# Camera_Board.net
KiCad netlist of a schematic drawn in EAGLE
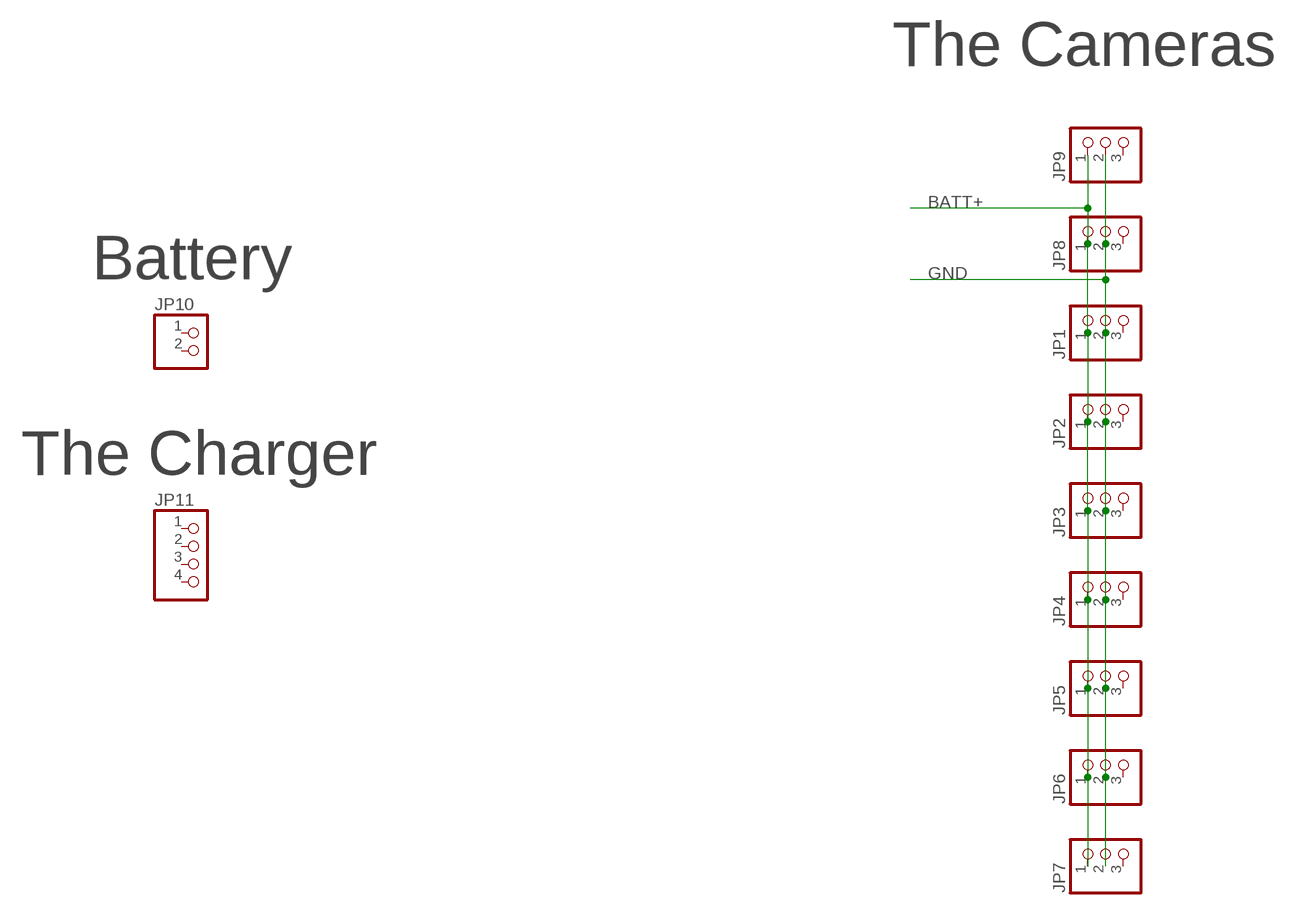
[diagram p0: schematic, sheet 1]

(export (version "E")
  (design (tool "Eeschema 10.0.6"))
  (components
    (comp (ref "JP1")
      (value "PINHD-1X3")
      (footprint "eagle-import:1X03")
      (libsource (lib "eagle-import") (part "PINHD-1X3"))
    )
    (comp (ref "JP2")
      (value "PINHD-1X3")
      (footprint "eagle-import:1X03")
      (libsource (lib "eagle-import") (part "PINHD-1X3"))
    )
    (comp (ref "JP3")
      (value "PINHD-1X3")
      (footprint "eagle-import:1X03")
      (libsource (lib "eagle-import") (part "PINHD-1X3"))
    )
    (comp (ref "JP4")
      (value "PINHD-1X3")
      (footprint "eagle-import:1X03")
      (libsource (lib "eagle-import") (part "PINHD-1X3"))
    )
    (comp (ref "JP5")
      (value "PINHD-1X3")
      (footprint "eagle-import:1X03")
      (libsource (lib "eagle-import") (part "PINHD-1X3"))
    )
    (comp (ref "JP6")
      (value "PINHD-1X3")
      (footprint "eagle-import:1X03")
      (libsource (lib "eagle-import") (part "PINHD-1X3"))
    )
    (comp (ref "JP7")
      (value "PINHD-1X3")
      (footprint "eagle-import:1X03")
      (libsource (lib "eagle-import") (part "PINHD-1X3"))
    )
    (comp (ref "JP8")
      (value "PINHD-1X3")
      (footprint "eagle-import:1X03")
      (libsource (lib "eagle-import") (part "PINHD-1X3"))
    )
    (comp (ref "JP9")
      (value "PINHD-1X3")
      (footprint "eagle-import:1X03")
      (libsource (lib "eagle-import") (part "PINHD-1X3"))
    )
    (comp (ref "JP10")
      (value "PINHD-1X2")
      (footprint "eagle-import:1X02")
      (libsource (lib "eagle-import") (part "PINHD-1X2"))
    )
    (comp (ref "JP11")
      (value "PINHD-1X4")
      (footprint "eagle-import:1X04")
      (libsource (lib "eagle-import") (part "PINHD-1X4"))
    )
  )
  (nets
    (net (code "1") (name "/BATT+") (class "Default")
      (node (ref "JP1") (pin "1") (pinfunction "1_1") (pintype "passive"))
      (node (ref "JP2") (pin "1") (pinfunction "1_1") (pintype "passive"))
      (node (ref "JP3") (pin "1") (pinfunction "1_1") (pintype "passive"))
      (node (ref "JP4") (pin "1") (pinfunction "1_1") (pintype "passive"))
      (node (ref "JP5") (pin "1") (pinfunction "1_1") (pintype "passive"))
      (node (ref "JP6") (pin "1") (pinfunction "1_1") (pintype "passive"))
      (node (ref "JP7") (pin "1") (pinfunction "1_1") (pintype "passive"))
      (node (ref "JP8") (pin "1") (pinfunction "1_1") (pintype "passive"))
      (node (ref "JP9") (pin "1") (pinfunction "1_1") (pintype "passive"))
    )
    (net (code "2") (name "/GND") (class "Default")
      (node (ref "JP1") (pin "2") (pinfunction "2_2") (pintype "passive"))
      (node (ref "JP2") (pin "2") (pinfunction "2_2") (pintype "passive"))
      (node (ref "JP3") (pin "2") (pinfunction "2_2") (pintype "passive"))
      (node (ref "JP4") (pin "2") (pinfunction "2_2") (pintype "passive"))
      (node (ref "JP5") (pin "2") (pinfunction "2_2") (pintype "passive"))
      (node (ref "JP6") (pin "2") (pinfunction "2_2") (pintype "passive"))
      (node (ref "JP7") (pin "2") (pinfunction "2_2") (pintype "passive"))
      (node (ref "JP8") (pin "2") (pinfunction "2_2") (pintype "passive"))
      (node (ref "JP9") (pin "2") (pinfunction "2_2") (pintype "passive"))
    )
    (net (code "3") (name "unconnected-(JP1-Pad3)") (class "Default")
      (node (ref "JP1") (pin "3") (pinfunction "3_3") (pintype "passive"))
    )
    (net (code "4") (name "unconnected-(JP2-Pad3)") (class "Default")
      (node (ref "JP2") (pin "3") (pinfunction "3_3") (pintype "passive"))
    )
    (net (code "5") (name "unconnected-(JP3-Pad3)") (class "Default")
      (node (ref "JP3") (pin "3") (pinfunction "3_3") (pintype "passive"))
    )
    (net (code "6") (name "unconnected-(JP4-Pad3)") (class "Default")
      (node (ref "JP4") (pin "3") (pinfunction "3_3") (pintype "passive"))
    )
    (net (code "7") (name "unconnected-(JP5-Pad3)") (class "Default")
      (node (ref "JP5") (pin "3") (pinfunction "3_3") (pintype "passive"))
    )
    (net (code "8") (name "unconnected-(JP6-Pad3)") (class "Default")
      (node (ref "JP6") (pin "3") (pinfunction "3_3") (pintype "passive"))
    )
    (net (code "9") (name "unconnected-(JP7-Pad3)") (class "Default")
      (node (ref "JP7") (pin "3") (pinfunction "3_3") (pintype "passive"))
    )
    (net (code "10") (name "unconnected-(JP8-Pad3)") (class "Default")
      (node (ref "JP8") (pin "3") (pinfunction "3_3") (pintype "passive"))
    )
    (net (code "11") (name "unconnected-(JP9-Pad3)") (class "Default")
      (node (ref "JP9") (pin "3") (pinfunction "3_3") (pintype "passive"))
    )
    (net (code "12") (name "unconnected-(JP10-Pad1)") (class "Default")
      (node (ref "JP10") (pin "1") (pinfunction "1_1") (pintype "passive"))
    )
    (net (code "13") (name "unconnected-(JP10-Pad2)") (class "Default")
      (node (ref "JP10") (pin "2") (pinfunction "2_2") (pintype "passive"))
    )
    (net (code "14") (name "unconnected-(JP11-Pad1)") (class "Default")
      (node (ref "JP11") (pin "1") (pinfunction "1_1") (pintype "passive"))
    )
    (net (code "15") (name "unconnected-(JP11-Pad2)") (class "Default")
      (node (ref "JP11") (pin "2") (pinfunction "2_2") (pintype "passive"))
    )
    (net (code "16") (name "unconnected-(JP11-Pad3)") (class "Default")
      (node (ref "JP11") (pin "3") (pinfunction "3_3") (pintype "passive"))
    )
    (net (code "17") (name "unconnected-(JP11-Pad4)") (class "Default")
      (node (ref "JP11") (pin "4") (pinfunction "4_4") (pintype "passive"))
    )
  )
)
